# Sheet1.net
KiCad netlist of a schematic drawn in Altium Designer
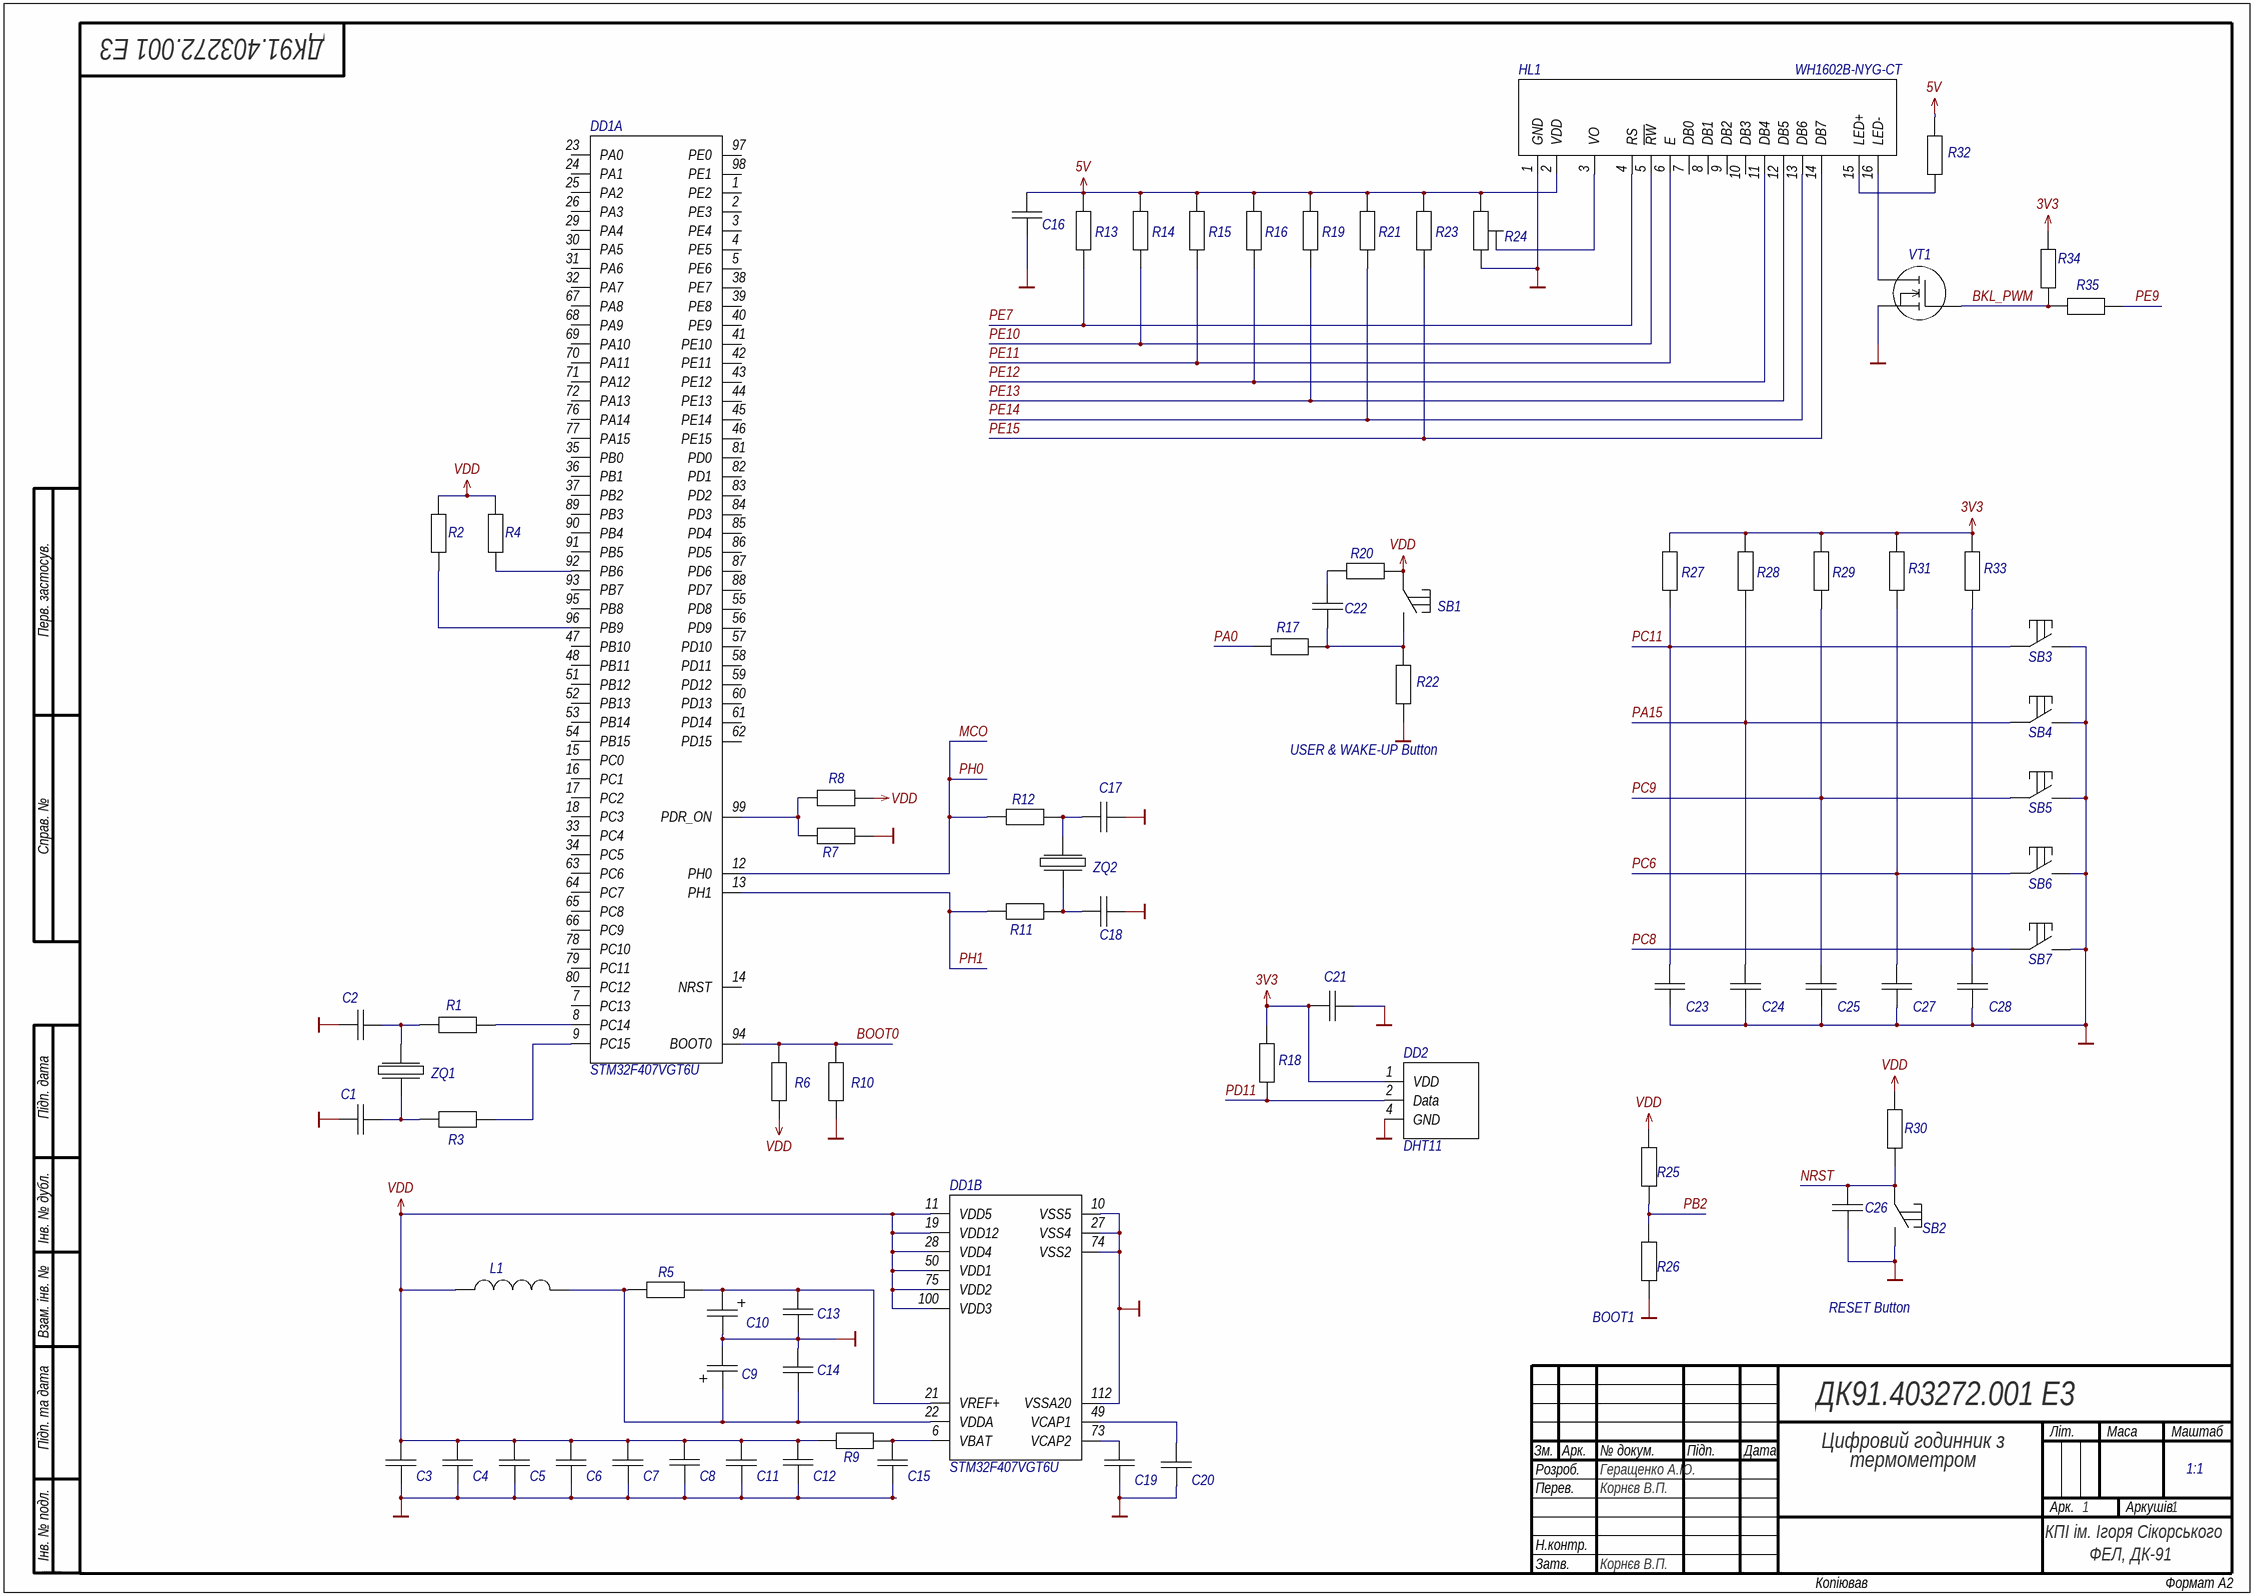
[diagram p0: Sheet1.SchDoc]

(export (version "E")
  (design (tool "Eeschema 10.0.6"))
  (components
    (comp (ref "C1")
      (value "0603 16 В 6,8 пФ 5% C0G, NP0 Kemet")
      (footprint "C-0603, 22 пФ")
      (description "Capasitor 0603")
      (fields (field (name "MANUFACTURER") "Kemet") (field (name "TOLERANCE") "5%"))
      (libsource (lib "Schlib1") (part "C-0603, 6,8 пФ"))
    )
    (comp (ref "C2")
      (value "0603 16 В 6,8 пФ 5% C0G, NP0 Kemet")
      (footprint "C-0603, 22 пФ")
      (description "Capasitor 0603")
      (fields (field (name "MANUFACTURER") "Kemet") (field (name "TOLERANCE") "5%"))
      (libsource (lib "Schlib1") (part "C-0603, 6,8 пФ"))
    )
    (comp (ref "C3")
      (value "0603 16 В 100 нФ 5% X7R Samsung")
      (footprint "C-0603, 100 нФ")
      (description "Capasitor 0603")
      (fields (field (name "MANUFACTURER") "Samsung") (field (name "TOLERANCE") "5%"))
      (libsource (lib "Schlib1") (part "C-0603, 100 нФ"))
    )
    (comp (ref "C4")
      (value "0603 16 В 100 нФ 5% X7R Samsung")
      (footprint "C-0603, 100 нФ")
      (description "Capasitor 0603")
      (fields (field (name "MANUFACTURER") "Samsung") (field (name "TOLERANCE") "5%"))
      (libsource (lib "Schlib1") (part "C-0603, 100 нФ"))
    )
    (comp (ref "C5")
      (value "0603 16 В 100 нФ 5% X7R Samsung")
      (footprint "C-0603, 100 нФ")
      (description "Capasitor 0603")
      (fields (field (name "MANUFACTURER") "Samsung") (field (name "TOLERANCE") "5%"))
      (libsource (lib "Schlib1") (part "C-0603, 100 нФ"))
    )
    (comp (ref "C6")
      (value "0603 16 В 100 нФ 5% X7R Samsung")
      (footprint "C-0603, 100 нФ")
      (description "Capasitor 0603")
      (fields (field (name "MANUFACTURER") "Samsung") (field (name "TOLERANCE") "5%"))
      (libsource (lib "Schlib1") (part "C-0603, 100 нФ"))
    )
    (comp (ref "C7")
      (value "0603 16 В 100 нФ 5% X7R Samsung")
      (footprint "C-0603, 100 нФ")
      (description "Capasitor 0603")
      (fields (field (name "MANUFACTURER") "Samsung") (field (name "TOLERANCE") "5%"))
      (libsource (lib "Schlib1") (part "C-0603, 100 нФ"))
    )
    (comp (ref "C8")
      (value "0603 16 В 100 нФ 5% X7R Samsung")
      (footprint "C-0603, 100 нФ")
      (description "Capasitor 0603")
      (fields (field (name "MANUFACTURER") "Samsung") (field (name "TOLERANCE") "5%"))
      (libsource (lib "Schlib1") (part "C-0603, 100 нФ"))
    )
    (comp (ref "C9")
      (value "1206 16 В 1 мкФ 10% KYOCERA AVX")
      (footprint "C-1206, 10 мкФ")
      (description "Capasitor")
      (fields (field (name "MANUFACTURER") "KYOCERA AVX") (field (name "TOLERANCE") "10%"))
      (libsource (lib "Schlib1") (part "С-1206, 1 мкФ"))
    )
    (comp (ref "C10")
      (value "1206 16 В 1 мкФ 10% KYOCERA AVX")
      (footprint "C-1206, 10 мкФ")
      (description "Capasitor")
      (fields (field (name "MANUFACTURER") "KYOCERA AVX") (field (name "TOLERANCE") "10%"))
      (libsource (lib "Schlib1") (part "С-1206, 1 мкФ"))
    )
    (comp (ref "C11")
      (value "0603 16 В 100 нФ 5% X7R Samsung")
      (footprint "C-0603, 100 нФ")
      (description "Capasitor 0603")
      (fields (field (name "MANUFACTURER") "Samsung") (field (name "TOLERANCE") "5%"))
      (libsource (lib "Schlib1") (part "C-0603, 100 нФ"))
    )
    (comp (ref "C12")
      (value "0603 16 В 100 нФ 5% X7R Samsung")
      (footprint "C-0603, 100 нФ")
      (description "Capasitor 0603")
      (fields (field (name "MANUFACTURER") "Samsung") (field (name "TOLERANCE") "5%"))
      (libsource (lib "Schlib1") (part "C-0603, 100 нФ"))
    )
    (comp (ref "C13")
      (value "0603 16 В 100 нФ 5% X7R Samsung")
      (footprint "C-0603, 100 нФ")
      (description "Capasitor 0603")
      (fields (field (name "MANUFACTURER") "Samsung") (field (name "TOLERANCE") "5%"))
      (libsource (lib "Schlib1") (part "C-0603, 100 нФ"))
    )
    (comp (ref "C14")
      (value "0603 16 В 100 нФ 5% X7R Samsung")
      (footprint "C-0603, 100 нФ")
      (description "Capasitor 0603")
      (fields (field (name "MANUFACTURER") "Samsung") (field (name "TOLERANCE") "5%"))
      (libsource (lib "Schlib1") (part "C-0603, 100 нФ"))
    )
    (comp (ref "C15")
      (value "0603 16 В 1 мкФ 5% X7R Kemet")
      (footprint "C-0603, 1 мкФ")
      (description "Capasitor 0603")
      (fields (field (name "MANUFACTURER") "Kemet") (field (name "TOLERANCE") "5%"))
      (libsource (lib "Schlib1") (part "C-0603, 1 мкФ"))
    )
    (comp (ref "C16")
      (value "0603 16 В 0,1 мкФ 5% X7R Kemet")
      (footprint "C-0603, 1 мкФ")
      (description "Capasitor 0603")
      (fields (field (name "MANUFACTURER") "Kemet") (field (name "TOLERANCE") "5%"))
      (libsource (lib "Schlib1") (part "C-0603, 0,1 мкФ"))
    )
    (comp (ref "C17")
      (value "0603 16 В 20 пФ 5% C0G, NP0 Kemet")
      (footprint "C-0603, 22 пФ")
      (description "Capasitor 0603")
      (fields (field (name "MANUFACTURER") "Kemet") (field (name "TOLERANCE") "5%"))
      (libsource (lib "Schlib1") (part "C-0603, 20 пФ"))
    )
    (comp (ref "C18")
      (value "0603 16 В 20 пФ 5% C0G, NP0 Kemet")
      (footprint "C-0603, 22 пФ")
      (description "Capasitor 0603")
      (fields (field (name "MANUFACTURER") "Kemet") (field (name "TOLERANCE") "5%"))
      (libsource (lib "Schlib1") (part "C-0603, 20 пФ"))
    )
    (comp (ref "C19")
      (value "0603 16 В 2,2 мкФ 5% X7R Kemet")
      (footprint "C-0603, 1 мкФ")
      (description "Capasitor 0603")
      (fields (field (name "MANUFACTURER") "Kemet") (field (name "TOLERANCE") "5%"))
      (libsource (lib "Schlib1") (part "C-0603, 2,2 мкФ"))
    )
    (comp (ref "C20")
      (value "0603 16 В 2,2 мкФ 5% X7R Kemet")
      (footprint "C-0603, 1 мкФ")
      (description "Capasitor 0603")
      (fields (field (name "MANUFACTURER") "Kemet") (field (name "TOLERANCE") "5%"))
      (libsource (lib "Schlib1") (part "C-0603, 2,2 мкФ"))
    )
    (comp (ref "C21")
      (value "0603 16 В 0,1 мкФ 5% X7R Kemet")
      (footprint "C-0603, 1 мкФ")
      (description "Capasitor 0603")
      (fields (field (name "MANUFACTURER") "Kemet") (field (name "TOLERANCE") "5%"))
      (libsource (lib "Schlib1") (part "C-0603, 0,1 мкФ"))
    )
    (comp (ref "C22")
      (value "0603 16 В 100 нФ 5% X7R Samsung")
      (footprint "C-0603, 100 нФ")
      (description "Capasitor 0603")
      (fields (field (name "MANUFACTURER") "Samsung") (field (name "TOLERANCE") "5%"))
      (libsource (lib "Schlib1") (part "C-0603, 100 нФ"))
    )
    (comp (ref "C23")
      (value "0603 16 В 0,01 мкФ 5% X7R Kemet")
      (footprint "C-0603, 1 мкФ")
      (description "Capasitor 0603")
      (fields (field (name "MANUFACTURER") "Kemet") (field (name "TOLERANCE") "5%"))
      (libsource (lib "Schlib1") (part "C-0603, 0,01 мкФ"))
    )
    (comp (ref "C24")
      (value "0603 16 В 0,01 мкФ 5% X7R Kemet")
      (footprint "C-0603, 1 мкФ")
      (description "Capasitor 0603")
      (fields (field (name "MANUFACTURER") "Kemet") (field (name "TOLERANCE") "5%"))
      (libsource (lib "Schlib1") (part "C-0603, 0,01 мкФ"))
    )
    (comp (ref "C25")
      (value "0603 16 В 0,01 мкФ 5% X7R Kemet")
      (footprint "C-0603, 1 мкФ")
      (description "Capasitor 0603")
      (fields (field (name "MANUFACTURER") "Kemet") (field (name "TOLERANCE") "5%"))
      (libsource (lib "Schlib1") (part "C-0603, 0,01 мкФ"))
    )
    (comp (ref "C26")
      (value "0603 16 В 100 нФ 5% X7R Samsung")
      (footprint "C-0603, 100 нФ")
      (description "Capasitor 0603")
      (fields (field (name "MANUFACTURER") "Samsung") (field (name "TOLERANCE") "5%"))
      (libsource (lib "Schlib1") (part "C-0603, 100 нФ"))
    )
    (comp (ref "C27")
      (value "0603 16 В 0,01 мкФ 5% X7R Kemet")
      (footprint "C-0603, 1 мкФ")
      (description "Capasitor 0603")
      (fields (field (name "MANUFACTURER") "Kemet") (field (name "TOLERANCE") "5%"))
      (libsource (lib "Schlib1") (part "C-0603, 0,01 мкФ"))
    )
    (comp (ref "C28")
      (value "0603 16 В 0,01 мкФ 5% X7R Kemet")
      (footprint "C-0603, 1 мкФ")
      (description "Capasitor 0603")
      (fields (field (name "MANUFACTURER") "Kemet") (field (name "TOLERANCE") "5%"))
      (libsource (lib "Schlib1") (part "C-0603, 0,01 мкФ"))
    )
    (comp (ref "DD1")
      (value "STM32F407VGT6U STMicroelectronics")
      (fields (field (name "NAME") "STM32F407VGT6U") (field (name "MANUFACTURER") "STMicroelectronics"))
      (libsource (lib "Schlib1") (part "STM32F407VGT6U"))
    )
    (comp (ref "DD2")
      (value "DHT11 Asair")
      (fields (field (name "NAME") "DHT11") (field (name "MANUFACTURER") "Asair"))
      (libsource (lib "Schlib1") (part "dht11"))
    )
    (comp (ref "HL1")
      (value "WH1602B-NYG-CT WINSTAR")
      (fields (field (name "NAME") "WH1602B-NYG-CT") (field (name "MANUFACTURER") "WINSTAR"))
      (libsource (lib "Schlib1") (part "lcd"))
    )
    (comp (ref "L1")
      (value "fcm1608-0603 Bourns Electronics")
      (footprint "IND_BOURNS_MH2029")
      (description "fcm1608-0603")
      (fields (field (name "MANUFACTURER") "Bourns Electronics"))
      (libsource (lib "Schlib1") (part "fcm1608-0603"))
    )
    (comp (ref "R1")
      (value "0603 0,1 Вт 0 Ом Jumper Panasonic")
      (footprint "R-0603, 0 Ом")
      (description "Resistor 0603")
      (fields (field (name "MANUFACTURER") "Panasonic") (field (name "TOLERANCE") "Jumper"))
      (libsource (lib "Schlib1") (part "R-0603, 0 Ом"))
    )
    (comp (ref "R2")
      (value "0603 0,25 Вт 4,7 кОм 5% Panasonic")
      (footprint "R-0603, 6,8 кОм")
      (description "Resistor 0603")
      (fields (field (name "MANUFACTURER") "Panasonic") (field (name "TOLERANCE") "5%"))
      (libsource (lib "Schlib1") (part "R-0603, 4,7 кОм"))
    )
    (comp (ref "R3")
      (value "0603 0,1 Вт 0 Ом Jumper Panasonic")
      (footprint "R-0603, 0 Ом")
      (description "Resistor 0603")
      (fields (field (name "MANUFACTURER") "Panasonic") (field (name "TOLERANCE") "Jumper"))
      (libsource (lib "Schlib1") (part "R-0603, 0 Ом"))
    )
    (comp (ref "R4")
      (value "0603 0,25 Вт 4,7 кОм 5% Panasonic")
      (footprint "R-0603, 6,8 кОм")
      (description "Resistor 0603")
      (fields (field (name "MANUFACTURER") "Panasonic") (field (name "TOLERANCE") "5%"))
      (libsource (lib "Schlib1") (part "R-0603, 4,7 кОм"))
    )
    (comp (ref "R5")
      (value "R-0603 0,1 Вт 47 Ом 5% Panasonic Electronic Components")
      (footprint "0603 47 Ом")
      (fields
        (field (name "POWER") "0,1 Вт")
        (field (name "TOLERANCE") "5%")
        (field (name "MANUFACTURER") "Panasonic Electronic Components")
      )
      (libsource (lib "Schlib1") (part "R-0603 47 Ом"))
    )
    (comp (ref "R6")
      (value "0603 0,25 Вт 10 кОм 5% Panasonic")
      (footprint "R-0603, 10 кОм")
      (description "Resistor 0603")
      (fields (field (name "MANUFACTURER") "Panasonic") (field (name "TOLERANCE") "5%"))
      (libsource (lib "Schlib1") (part "R-0603, 10 кОм"))
    )
    (comp (ref "R7")
      (value "0603 0,1 Вт 0 Ом Jumper Panasonic")
      (footprint "R-0603, 0 Ом")
      (description "Resistor 0603")
      (fields (field (name "MANUFACTURER") "Panasonic") (field (name "TOLERANCE") "Jumper"))
      (libsource (lib "Schlib1") (part "R-0603, 0 Ом"))
    )
    (comp (ref "R8")
      (value "0603 0,1 Вт 0 Ом Jumper Panasonic")
      (footprint "R-0603, 0 Ом")
      (description "Resistor 0603")
      (fields (field (name "MANUFACTURER") "Panasonic") (field (name "TOLERANCE") "Jumper"))
      (libsource (lib "Schlib1") (part "R-0603, 0 Ом"))
    )
    (comp (ref "R9")
      (value "0603 0,1 Вт 0 Ом Jumper Panasonic")
      (footprint "R-0603, 0 Ом")
      (description "Resistor 0603")
      (fields (field (name "MANUFACTURER") "Panasonic") (field (name "TOLERANCE") "Jumper"))
      (libsource (lib "Schlib1") (part "R-0603, 0 Ом"))
    )
    (comp (ref "R10")
      (value "R-0603 0,1 Вт 510 Ом 5% Panasonic Electronic Components")
      (footprint "0603 330 Ом")
      (fields
        (field (name "POWER") "0,1 Вт")
        (field (name "TOLERANCE") "5%")
        (field (name "MANUFACTURER") "Panasonic Electronic Components")
      )
      (libsource (lib "Schlib1") (part "R-0603 510 Ом"))
    )
    (comp (ref "R11")
      (value "R-0603 0,1 Вт 220 Ом 5% Panasonic Electronic Components")
      (footprint "0603 270 Ом")
      (fields
        (field (name "POWER") "0,1 Вт")
        (field (name "TOLERANCE") "5%")
        (field (name "MANUFACTURER") "Panasonic Electronic Components")
      )
      (libsource (lib "Schlib1") (part "R-0603 220 Ом"))
    )
    (comp (ref "R12")
      (value "0603 0,1 Вт 0 Ом Jumper Panasonic")
      (footprint "R-0603, 0 Ом")
      (description "Resistor 0603")
      (fields (field (name "MANUFACTURER") "Panasonic") (field (name "TOLERANCE") "Jumper"))
      (libsource (lib "Schlib1") (part "R-0603, 0 Ом"))
    )
    (comp (ref "R13")
      (value "0603 0,25 Вт 4,7 кОм 5% Panasonic")
      (footprint "R-0603, 6,8 кОм")
      (description "Resistor 0603")
      (fields (field (name "MANUFACTURER") "Panasonic") (field (name "TOLERANCE") "5%"))
      (libsource (lib "Schlib1") (part "R-0603, 4,7 кОм"))
    )
    (comp (ref "R14")
      (value "0603 0,25 Вт 4,7 кОм 5% Panasonic")
      (footprint "R-0603, 6,8 кОм")
      (description "Resistor 0603")
      (fields (field (name "MANUFACTURER") "Panasonic") (field (name "TOLERANCE") "5%"))
      (libsource (lib "Schlib1") (part "R-0603, 4,7 кОм"))
    )
    (comp (ref "R15")
      (value "0603 0,25 Вт 4,7 кОм 5% Panasonic")
      (footprint "R-0603, 6,8 кОм")
      (description "Resistor 0603")
      (fields (field (name "MANUFACTURER") "Panasonic") (field (name "TOLERANCE") "5%"))
      (libsource (lib "Schlib1") (part "R-0603, 4,7 кОм"))
    )
    (comp (ref "R16")
      (value "0603 0,25 Вт 4,7 кОм 5% Panasonic")
      (footprint "R-0603, 6,8 кОм")
      (description "Resistor 0603")
      (fields (field (name "MANUFACTURER") "Panasonic") (field (name "TOLERANCE") "5%"))
      (libsource (lib "Schlib1") (part "R-0603, 4,7 кОм"))
    )
    (comp (ref "R17")
      (value "R-0603 0,1 Вт 330 Ом 5% Panasonic Electronic Components")
      (footprint "0603 330 Ом")
      (fields
        (field (name "POWER") "0,1 Вт")
        (field (name "TOLERANCE") "5%")
        (field (name "MANUFACTURER") "Panasonic Electronic Components")
      )
      (libsource (lib "Schlib1") (part "R-0603 330 Ом"))
    )
    (comp (ref "R18")
      (value "0603 0,25 Вт 2 кОм 5% Panasonic")
      (footprint "R-0603, 1кОм")
      (description "Resistor 0603")
      (fields (field (name "MANUFACTURER") "Panasonic") (field (name "TOLERANCE") "5%"))
      (libsource (lib "Schlib1") (part "R-0603, 2кОм"))
    )
    (comp (ref "R19")
      (value "0603 0,25 Вт 4,7 кОм 5% Panasonic")
      (footprint "R-0603, 6,8 кОм")
      (description "Resistor 0603")
      (fields (field (name "MANUFACTURER") "Panasonic") (field (name "TOLERANCE") "5%"))
      (libsource (lib "Schlib1") (part "R-0603, 4,7 кОм"))
    )
    (comp (ref "R20")
      (value "R-0603  100 Ом 5% Panasonic Electronic Components")
      (footprint "0603 100 Ом")
      (fields (field (name "TOLERANCE") "5%") (field (name "MANUFACTURER") "Panasonic Electronic Components"))
      (libsource (lib "Schlib1") (part "R-0603 100 Ом"))
    )
    (comp (ref "R21")
      (value "0603 0,25 Вт 4,7 кОм 5% Panasonic")
      (footprint "R-0603, 6,8 кОм")
      (description "Resistor 0603")
      (fields (field (name "MANUFACTURER") "Panasonic") (field (name "TOLERANCE") "5%"))
      (libsource (lib "Schlib1") (part "R-0603, 4,7 кОм"))
    )
    (comp (ref "R22")
      (value "R-0603 0,1 Вт 220 кОм 5% Panasonic Electronic Components")
      (footprint "0603 330 кОм")
      (fields
        (field (name "POWER") "0,1 Вт")
        (field (name "TOLERANCE") "5%")
        (field (name "MANUFACTURER") "Panasonic Electronic Components")
      )
      (libsource (lib "Schlib1") (part "R-0603 220 кОм"))
    )
    (comp (ref "R23")
      (value "0603 0,25 Вт 4,7 кОм 5% Panasonic")
      (footprint "R-0603, 6,8 кОм")
      (description "Resistor 0603")
      (fields (field (name "MANUFACTURER") "Panasonic") (field (name "TOLERANCE") "5%"))
      (libsource (lib "Schlib1") (part "R-0603, 4,7 кОм"))
    )
    (comp (ref "R24")
      (value "Tube 0,5 Вт 10 кОм 10% Bourns Inc.")
      (footprint "R-Tube")
      (fields
        (field (name "POWER") "0,5 Вт")
        (field (name "TOLERANCE") "10%")
        (field (name "MANUFACTURER") "Bourns Inc.")
      )
      (libsource (lib "Schlib1") (part "R-Tube 10 кОм"))
    )
    (comp (ref "R25")
      (value "0603 0,25 Вт 10 кОм 5% Panasonic")
      (footprint "R-0603, 10 кОм")
      (description "Resistor 0603")
      (fields (field (name "MANUFACTURER") "Panasonic") (field (name "TOLERANCE") "5%"))
      (libsource (lib "Schlib1") (part "R-0603, 10 кОм"))
    )
    (comp (ref "R26")
      (value "R-0603 0,1 Вт 510 Ом 5% Panasonic Electronic Components")
      (footprint "0603 330 Ом")
      (fields
        (field (name "POWER") "0,1 Вт")
        (field (name "TOLERANCE") "5%")
        (field (name "MANUFACTURER") "Panasonic Electronic Components")
      )
      (libsource (lib "Schlib1") (part "R-0603 510 Ом"))
    )
    (comp (ref "R27")
      (value "0603 0,25 Вт 4,7 кОм 5% Panasonic")
      (footprint "R-0603, 6,8 кОм")
      (description "Resistor 0603")
      (fields (field (name "MANUFACTURER") "Panasonic") (field (name "TOLERANCE") "5%"))
      (libsource (lib "Schlib1") (part "R-0603, 4,7 кОм"))
    )
    (comp (ref "R28")
      (value "0603 0,25 Вт 4,7 кОм 5% Panasonic")
      (footprint "R-0603, 6,8 кОм")
      (description "Resistor 0603")
      (fields (field (name "MANUFACTURER") "Panasonic") (field (name "TOLERANCE") "5%"))
      (libsource (lib "Schlib1") (part "R-0603, 4,7 кОм"))
    )
    (comp (ref "R29")
      (value "0603 0,25 Вт 4,7 кОм 5% Panasonic")
      (footprint "R-0603, 6,8 кОм")
      (description "Resistor 0603")
      (fields (field (name "MANUFACTURER") "Panasonic") (field (name "TOLERANCE") "5%"))
      (libsource (lib "Schlib1") (part "R-0603, 4,7 кОм"))
    )
    (comp (ref "R30")
      (value "0603 0,25 Вт 100 кОм 5% Panasonic")
      (footprint "R-0603, 100 кОм")
      (description "Resistor 0603")
      (fields (field (name "MANUFACTURER") "Panasonic") (field (name "TOLERANCE") "5%"))
      (libsource (lib "Schlib1") (part "R-0603, 100 кОм"))
    )
    (comp (ref "R31")
      (value "0603 0,25 Вт 4,7 кОм 5% Panasonic")
      (footprint "R-0603, 6,8 кОм")
      (description "Resistor 0603")
      (fields (field (name "MANUFACTURER") "Panasonic") (field (name "TOLERANCE") "5%"))
      (libsource (lib "Schlib1") (part "R-0603, 4,7 кОм"))
    )
    (comp (ref "R32")
      (value "R-0603  100 Ом 5% Panasonic Electronic Components")
      (footprint "0603 100 Ом")
      (fields (field (name "TOLERANCE") "5%") (field (name "MANUFACTURER") "Panasonic Electronic Components"))
      (libsource (lib "") (part "R-0603 100 Ом_1"))
    )
    (comp (ref "R33")
      (value "0603 0,25 Вт 4,7 кОм 5% Panasonic")
      (footprint "R-0603, 6,8 кОм")
      (description "Resistor 0603")
      (fields (field (name "MANUFACTURER") "Panasonic") (field (name "TOLERANCE") "5%"))
      (libsource (lib "Schlib1") (part "R-0603, 4,7 кОм"))
    )
    (comp (ref "R34")
      (value "0603 0,25 Вт 4,7 кОм 5% Panasonic")
      (footprint "R-0603, 6,8 кОм")
      (description "Resistor 0603")
      (fields (field (name "MANUFACTURER") "Panasonic") (field (name "TOLERANCE") "5%"))
      (libsource (lib "Schlib1") (part "R-0603, 4,7 кОм"))
    )
    (comp (ref "R35")
      (value "R-0603  100 Ом 5% Panasonic Electronic Components")
      (footprint "0603 100 Ом")
      (fields (field (name "TOLERANCE") "5%") (field (name "MANUFACTURER") "Panasonic Electronic Components"))
      (libsource (lib "Schlib1") (part "R-0603 100 Ом"))
    )
    (comp (ref "SB1")
      (value "RS032G05A3SMRT C&K")
      (footprint "SB 2 pin")
      (description "Tactile Switch SPST-NO Top Actuated Surface Mount")
      (fields (field (name "MANUFACTURER") "C&K"))
      (libsource (lib "Schlib1") (part "SB 2pin"))
    )
    (comp (ref "SB2")
      (value "RS032G05A3SMRT C&K")
      (footprint "SB 2 pin")
      (description "Tactile Switch SPST-NO Top Actuated Surface Mount")
      (fields (field (name "MANUFACTURER") "C&K"))
      (libsource (lib "Schlib1") (part "SB 2pin"))
    )
    (comp (ref "SB3")
      (value "RS032G05A3SMRT C&K")
      (footprint "SB 2 pin")
      (description "Tactile Switch SPST-NO Top Actuated Surface Mount")
      (fields (field (name "MANUFACTURER") "C&K"))
      (libsource (lib "Schlib1") (part "SB 2pin"))
    )
    (comp (ref "SB4")
      (value "RS032G05A3SMRT C&K")
      (footprint "SB 2 pin")
      (description "Tactile Switch SPST-NO Top Actuated Surface Mount")
      (fields (field (name "MANUFACTURER") "C&K"))
      (libsource (lib "Schlib1") (part "SB 2pin"))
    )
    (comp (ref "SB5")
      (value "RS032G05A3SMRT C&K")
      (footprint "SB 2 pin")
      (description "Tactile Switch SPST-NO Top Actuated Surface Mount")
      (fields (field (name "MANUFACTURER") "C&K"))
      (libsource (lib "Schlib1") (part "SB 2pin"))
    )
    (comp (ref "SB6")
      (value "RS032G05A3SMRT C&K")
      (footprint "SB 2 pin")
      (description "Tactile Switch SPST-NO Top Actuated Surface Mount")
      (fields (field (name "MANUFACTURER") "C&K"))
      (libsource (lib "Schlib1") (part "SB 2pin"))
    )
    (comp (ref "SB7")
      (value "RS032G05A3SMRT C&K")
      (footprint "SB 2 pin")
      (description "Tactile Switch SPST-NO Top Actuated Surface Mount")
      (fields (field (name "MANUFACTURER") "C&K"))
      (libsource (lib "Schlib1") (part "SB 2pin"))
    )
    (comp (ref "VT1")
      (value "IRLML2402TRPBF Infineon Technologies")
      (footprint "VT IRFZ44NLPBF")
      (fields (field (name "MANUFACTURER") "Infineon Technologies"))
      (libsource (lib "Schlib1") (part "VT IRLML2402TRPBF"))
    )
    (comp (ref "ZQ1")
      (value "MC306-G-06Q-32.768 JFVNY")
      (footprint "ZQ 32,768 kHz")
      (fields (field (name "MANUFACTURER") "JFVNY"))
      (libsource (lib "Schlib1") (part "ZQ 32,768 kHz"))
    )
    (comp (ref "ZQ2")
      (value "J49SMH-P-G-G-K-8M0 Jauch Quartz")
      (footprint "ZQ 32,768 kHz")
      (fields (field (name "MANUFACTURER") "Jauch Quartz"))
      (libsource (lib "Schlib1") (part "ZQ 8 MHz"))
    )
  )
  (nets
    (net (code "1") (name "/BKL_PWM") (class "Default")
      (node (ref "R34") (pin "1") (pinfunction "1_1") (pintype "passive"))
      (node (ref "R35") (pin "1") (pinfunction "1_1") (pintype "passive"))
      (node (ref "VT1") (pin "1") (pinfunction "1_1") (pintype "passive"))
    )
    (net (code "2") (name "/BOOT0") (class "Default")
      (node (ref "DD1") (pin "94") (pinfunction "BOOT0_94") (pintype "passive"))
      (node (ref "R10") (pin "2") (pinfunction "2_2") (pintype "passive"))
      (node (ref "R6") (pin "2") (pinfunction "2_2") (pintype "passive"))
    )
    (net (code "3") (name "/MCO") (class "Default")
      (node (ref "DD1") (pin "12") (pinfunction "PH0_12") (pintype "passive"))
      (node (ref "R12") (pin "1") (pinfunction "1_1") (pintype "passive"))
    )
    (net (code "4") (name "/NRST") (class "Default")
      (node (ref "C26") (pin "2") (pinfunction "2_2") (pintype "passive"))
      (node (ref "R30") (pin "1") (pinfunction "1_1") (pintype "passive"))
      (node (ref "SB2") (pin "1") (pinfunction "1_1") (pintype "passive"))
    )
    (net (code "5") (name "/PA0") (class "Default")
      (node (ref "R17") (pin "1") (pinfunction "1_1") (pintype "passive"))
    )
    (net (code "6") (name "/PA15") (class "Default")
      (node (ref "C24") (pin "2") (pinfunction "2_2") (pintype "passive"))
      (node (ref "R28") (pin "1") (pinfunction "1_1") (pintype "passive"))
      (node (ref "SB4") (pin "1") (pinfunction "1_1") (pintype "passive"))
    )
    (net (code "7") (name "/PB2") (class "Default")
      (node (ref "R25") (pin "1") (pinfunction "1_1") (pintype "passive"))
      (node (ref "R26") (pin "2") (pinfunction "2_2") (pintype "passive"))
    )
    (net (code "8") (name "/PC6") (class "Default")
      (node (ref "C27") (pin "2") (pinfunction "2_2") (pintype "passive"))
      (node (ref "R31") (pin "1") (pinfunction "1_1") (pintype "passive"))
      (node (ref "SB6") (pin "1") (pinfunction "1_1") (pintype "passive"))
    )
    (net (code "9") (name "/PC8") (class "Default")
      (node (ref "C28") (pin "2") (pinfunction "2_2") (pintype "passive"))
      (node (ref "R33") (pin "1") (pinfunction "1_1") (pintype "passive"))
      (node (ref "SB7") (pin "1") (pinfunction "1_1") (pintype "passive"))
    )
    (net (code "10") (name "/PC9") (class "Default")
      (node (ref "C25") (pin "2") (pinfunction "2_2") (pintype "passive"))
      (node (ref "R29") (pin "1") (pinfunction "1_1") (pintype "passive"))
      (node (ref "SB5") (pin "1") (pinfunction "1_1") (pintype "passive"))
    )
    (net (code "11") (name "/PC11") (class "Default")
      (node (ref "C23") (pin "2") (pinfunction "2_2") (pintype "passive"))
      (node (ref "R27") (pin "1") (pinfunction "1_1") (pintype "passive"))
      (node (ref "SB3") (pin "1") (pinfunction "1_1") (pintype "passive"))
    )
    (net (code "12") (name "/PD11") (class "Default")
      (node (ref "DD2") (pin "2") (pinfunction "Data_2") (pintype "passive"))
      (node (ref "R18") (pin "1") (pinfunction "1_1") (pintype "passive"))
    )
    (net (code "13") (name "/PE7") (class "Default")
      (node (ref "HL1") (pin "4") (pinfunction "RS_4") (pintype "passive"))
      (node (ref "R13") (pin "1") (pinfunction "1_1") (pintype "passive"))
    )
    (net (code "14") (name "/PE9") (class "Default")
      (node (ref "R35") (pin "2") (pinfunction "2_2") (pintype "passive"))
    )
    (net (code "15") (name "/PE10") (class "Default")
      (node (ref "HL1") (pin "5") (pinfunction "~{RW}_5") (pintype "passive"))
      (node (ref "R14") (pin "1") (pinfunction "1_1") (pintype "passive"))
    )
    (net (code "16") (name "/PE11") (class "Default")
      (node (ref "HL1") (pin "6") (pinfunction "E_6") (pintype "passive"))
      (node (ref "R15") (pin "1") (pinfunction "1_1") (pintype "passive"))
    )
    (net (code "17") (name "/PE12") (class "Default")
      (node (ref "HL1") (pin "11") (pinfunction "DB4_11") (pintype "passive"))
      (node (ref "R16") (pin "1") (pinfunction "1_1") (pintype "passive"))
    )
    (net (code "18") (name "/PE13") (class "Default")
      (node (ref "HL1") (pin "12") (pinfunction "DB5_12") (pintype "passive"))
      (node (ref "R19") (pin "1") (pinfunction "1_1") (pintype "passive"))
    )
    (net (code "19") (name "/PE14") (class "Default")
      (node (ref "HL1") (pin "13") (pinfunction "DB6_13") (pintype "passive"))
      (node (ref "R21") (pin "1") (pinfunction "1_1") (pintype "passive"))
    )
    (net (code "20") (name "/PE15") (class "Default")
      (node (ref "HL1") (pin "14") (pinfunction "DB7_14") (pintype "passive"))
      (node (ref "R23") (pin "1") (pinfunction "1_1") (pintype "passive"))
    )
    (net (code "21") (name "/PH1") (class "Default")
      (node (ref "DD1") (pin "13") (pinfunction "PH1_13") (pintype "passive"))
      (node (ref "R11") (pin "1") (pinfunction "1_1") (pintype "passive"))
    )
    (net (code "22") (name "3V3") (class "Default")
      (node (ref "C21") (pin "1") (pinfunction "1_1") (pintype "passive"))
      (node (ref "DD2") (pin "1") (pinfunction "VDD_1") (pintype "passive"))
      (node (ref "R18") (pin "2") (pinfunction "2_2") (pintype "passive"))
      (node (ref "R27") (pin "2") (pinfunction "2_2") (pintype "passive"))
      (node (ref "R28") (pin "2") (pinfunction "2_2") (pintype "passive"))
      (node (ref "R29") (pin "2") (pinfunction "2_2") (pintype "passive"))
      (node (ref "R31") (pin "2") (pinfunction "2_2") (pintype "passive"))
      (node (ref "R33") (pin "2") (pinfunction "2_2") (pintype "passive"))
      (node (ref "R34") (pin "2") (pinfunction "2_2") (pintype "passive"))
    )
    (net (code "23") (name "5V") (class "Default")
      (node (ref "C16") (pin "2") (pinfunction "2_2") (pintype "passive"))
      (node (ref "HL1") (pin "2") (pinfunction "VDD_2") (pintype "passive"))
      (node (ref "R13") (pin "2") (pinfunction "2_2") (pintype "passive"))
      (node (ref "R14") (pin "2") (pinfunction "2_2") (pintype "passive"))
      (node (ref "R15") (pin "2") (pinfunction "2_2") (pintype "passive"))
      (node (ref "R16") (pin "2") (pinfunction "2_2") (pintype "passive"))
      (node (ref "R19") (pin "2") (pinfunction "2_2") (pintype "passive"))
      (node (ref "R21") (pin "2") (pinfunction "2_2") (pintype "passive"))
      (node (ref "R23") (pin "2") (pinfunction "2_2") (pintype "passive"))
      (node (ref "R24") (pin "1") (pinfunction "1_1") (pintype "passive"))
      (node (ref "R32") (pin "2") (pinfunction "2_2") (pintype "passive"))
    )
    (net (code "24") (name "GND") (class "Default")
      (node (ref "C1") (pin "1") (pinfunction "1_1") (pintype "passive"))
      (node (ref "C10") (pin "2") (pinfunction "2_2") (pintype "passive"))
      (node (ref "C11") (pin "1") (pinfunction "1_1") (pintype "passive"))
      (node (ref "C12") (pin "2") (pinfunction "2_2") (pintype "passive"))
      (node (ref "C13") (pin "1") (pinfunction "1_1") (pintype "passive"))
      (node (ref "C14") (pin "1") (pinfunction "1_1") (pintype "passive"))
      (node (ref "C15") (pin "1") (pinfunction "1_1") (pintype "passive"))
      (node (ref "C16") (pin "1") (pinfunction "1_1") (pintype "passive"))
      (node (ref "C17") (pin "2") (pinfunction "2_2") (pintype "passive"))
      (node (ref "C18") (pin "2") (pinfunction "2_2") (pintype "passive"))
      (node (ref "C19") (pin "1") (pinfunction "1_1") (pintype "passive"))
      (node (ref "C2") (pin "1") (pinfunction "1_1") (pintype "passive"))
      (node (ref "C20") (pin "1") (pinfunction "1_1") (pintype "passive"))
      (node (ref "C21") (pin "2") (pinfunction "2_2") (pintype "passive"))
      (node (ref "C23") (pin "1") (pinfunction "1_1") (pintype "passive"))
      (node (ref "C24") (pin "1") (pinfunction "1_1") (pintype "passive"))
      (node (ref "C25") (pin "1") (pinfunction "1_1") (pintype "passive"))
      (node (ref "C26") (pin "1") (pinfunction "1_1") (pintype "passive"))
      (node (ref "C27") (pin "1") (pinfunction "1_1") (pintype "passive"))
      (node (ref "C28") (pin "1") (pinfunction "1_1") (pintype "passive"))
      (node (ref "C3") (pin "1") (pinfunction "1_1") (pintype "passive"))
      (node (ref "C4") (pin "1") (pinfunction "1_1") (pintype "passive"))
      (node (ref "C5") (pin "1") (pinfunction "1_1") (pintype "passive"))
      (node (ref "C6") (pin "1") (pinfunction "1_1") (pintype "passive"))
      (node (ref "C7") (pin "1") (pinfunction "1_1") (pintype "passive"))
      (node (ref "C8") (pin "2") (pinfunction "2_2") (pintype "passive"))
      (node (ref "C9") (pin "2") (pinfunction "2_2") (pintype "passive"))
      (node (ref "DD1") (pin "10") (pinfunction "VSS5_10") (pintype "passive"))
      (node (ref "DD1") (pin "112") (pinfunction "VSSA20_112") (pintype "passive"))
      (node (ref "DD1") (pin "27") (pinfunction "VSS4_27") (pintype "passive"))
      (node (ref "DD1") (pin "74") (pinfunction "VSS2_74") (pintype "passive"))
      (node (ref "DD2") (pin "4") (pinfunction "GND_4") (pintype "passive"))
      (node (ref "HL1") (pin "1") (pinfunction "GND_1") (pintype "passive"))
      (node (ref "R10") (pin "1") (pinfunction "1_1") (pintype "passive"))
      (node (ref "R22") (pin "1") (pinfunction "1_1") (pintype "passive"))
      (node (ref "R24") (pin "3") (pinfunction "3_3") (pintype "passive"))
      (node (ref "R26") (pin "1") (pinfunction "1_1") (pintype "passive"))
      (node (ref "R7") (pin "2") (pinfunction "2_2") (pintype "passive"))
      (node (ref "SB2") (pin "2") (pinfunction "2_2") (pintype "passive"))
      (node (ref "SB3") (pin "2") (pinfunction "2_2") (pintype "passive"))
      (node (ref "SB4") (pin "2") (pinfunction "2_2") (pintype "passive"))
      (node (ref "SB5") (pin "2") (pinfunction "2_2") (pintype "passive"))
      (node (ref "SB6") (pin "2") (pinfunction "2_2") (pintype "passive"))
      (node (ref "SB7") (pin "2") (pinfunction "2_2") (pintype "passive"))
      (node (ref "VT1") (pin "3") (pinfunction "3_3") (pintype "passive"))
    )
    (net (code "25") (name "Net-(C22-Pad1)") (class "Default")
      (node (ref "C22") (pin "1") (pinfunction "1_1") (pintype "passive"))
      (node (ref "R17") (pin "2") (pinfunction "2_2") (pintype "passive"))
      (node (ref "R22") (pin "2") (pinfunction "2_2") (pintype "passive"))
      (node (ref "SB1") (pin "2") (pinfunction "2_2") (pintype "passive"))
    )
    (net (code "26") (name "Net-(C22-Pad2)") (class "Default")
      (node (ref "C22") (pin "2") (pinfunction "2_2") (pintype "passive"))
      (node (ref "R20") (pin "1") (pinfunction "1_1") (pintype "passive"))
    )
    (net (code "27") (name "Net-(DD1A-PB6)") (class "Default")
      (node (ref "DD1") (pin "92") (pinfunction "PB6_92") (pintype "passive"))
      (node (ref "R4") (pin "1") (pinfunction "1_1") (pintype "passive"))
    )
    (net (code "28") (name "Net-(DD1A-PB9)") (class "Default")
      (node (ref "DD1") (pin "96") (pinfunction "PB9_96") (pintype "passive"))
      (node (ref "R2") (pin "1") (pinfunction "1_1") (pintype "passive"))
    )
    (net (code "29") (name "Net-(DD1A-PC14)") (class "Default")
      (node (ref "DD1") (pin "8") (pinfunction "PC14_8") (pintype "passive"))
      (node (ref "R1") (pin "2") (pinfunction "2_2") (pintype "passive"))
    )
    (net (code "30") (name "Net-(DD1A-PC15)") (class "Default")
      (node (ref "DD1") (pin "9") (pinfunction "PC15_9") (pintype "passive"))
      (node (ref "R3") (pin "2") (pinfunction "2_2") (pintype "passive"))
    )
    (net (code "31") (name "Net-(DD1A-PDR_ON)") (class "Default")
      (node (ref "DD1") (pin "99") (pinfunction "PDR_ON_99") (pintype "passive"))
      (node (ref "R7") (pin "1") (pinfunction "1_1") (pintype "passive"))
      (node (ref "R8") (pin "1") (pinfunction "1_1") (pintype "passive"))
    )
    (net (code "32") (name "Net-(DD1B-VBAT)") (class "Default")
      (node (ref "C15") (pin "2") (pinfunction "2_2") (pintype "passive"))
      (node (ref "DD1") (pin "6") (pinfunction "VBAT_6") (pintype "passive"))
      (node (ref "R9") (pin "2") (pinfunction "2_2") (pintype "passive"))
    )
    (net (code "33") (name "Net-(DD1B-VCAP1)") (class "Default")
      (node (ref "C20") (pin "2") (pinfunction "2_2") (pintype "passive"))
      (node (ref "DD1") (pin "49") (pinfunction "VCAP1_49") (pintype "passive"))
    )
    (net (code "34") (name "Net-(DD1B-VCAP2)") (class "Default")
      (node (ref "C19") (pin "2") (pinfunction "2_2") (pintype "passive"))
      (node (ref "DD1") (pin "73") (pinfunction "VCAP2_73") (pintype "passive"))
    )
    (net (code "35") (name "Net-(DD1B-VDDA)") (class "Default")
      (node (ref "C14") (pin "2") (pinfunction "2_2") (pintype "passive"))
      (node (ref "C9") (pin "1") (pinfunction "1_1") (pintype "passive"))
      (node (ref "DD1") (pin "22") (pinfunction "VDDA_22") (pintype "passive"))
      (node (ref "L1") (pin "2") (pinfunction "2_2") (pintype "passive"))
      (node (ref "R5") (pin "1") (pinfunction "1_1") (pintype "passive"))
    )
    (net (code "36") (name "Net-(DD1B-VREF+)") (class "Default")
      (node (ref "C10") (pin "1") (pinfunction "1_1") (pintype "passive"))
      (node (ref "C13") (pin "2") (pinfunction "2_2") (pintype "passive"))
      (node (ref "DD1") (pin "21") (pinfunction "VREF+_21") (pintype "passive"))
      (node (ref "R5") (pin "2") (pinfunction "2_2") (pintype "passive"))
    )
    (net (code "37") (name "Net-(HL1-LED+)") (class "Default")
      (node (ref "HL1") (pin "15") (pinfunction "LED+_15") (pintype "passive"))
      (node (ref "R32") (pin "1") (pinfunction "1_1") (pintype "passive"))
    )
    (net (code "38") (name "Net-(HL1-LED-)") (class "Default")
      (node (ref "HL1") (pin "16") (pinfunction "LED-_16") (pintype "passive"))
      (node (ref "VT1") (pin "2") (pinfunction "2_2") (pintype "passive"))
    )
    (net (code "39") (name "Net-(HL1-VO)") (class "Default")
      (node (ref "HL1") (pin "3") (pinfunction "VO_3") (pintype "passive"))
      (node (ref "R24") (pin "2") (pinfunction "2_2") (pintype "passive"))
    )
    (net (code "40") (name "Net-(ZQ1-In{slash}Out)") (class "Default")
      (node (ref "C1") (pin "2") (pinfunction "2_2") (pintype "passive"))
      (node (ref "R3") (pin "1") (pinfunction "1_1") (pintype "passive"))
      (node (ref "ZQ1") (pin "1") (pinfunction "In/Out_1") (pintype "passive"))
    )
    (net (code "41") (name "Net-(ZQ1-Out{slash}In)") (class "Default")
      (node (ref "C2") (pin "2") (pinfunction "2_2") (pintype "passive"))
      (node (ref "R1") (pin "1") (pinfunction "1_1") (pintype "passive"))
      (node (ref "ZQ1") (pin "2") (pinfunction "Out/In_2") (pintype "passive"))
    )
    (net (code "42") (name "Net-(ZQ2-In{slash}Out)") (class "Default")
      (node (ref "C18") (pin "1") (pinfunction "1_1") (pintype "passive"))
      (node (ref "R11") (pin "2") (pinfunction "2_2") (pintype "passive"))
      (node (ref "ZQ2") (pin "1") (pinfunction "In/Out_1") (pintype "passive"))
    )
    (net (code "43") (name "Net-(ZQ2-Out{slash}In)") (class "Default")
      (node (ref "C17") (pin "1") (pinfunction "1_1") (pintype "passive"))
      (node (ref "R12") (pin "2") (pinfunction "2_2") (pintype "passive"))
      (node (ref "ZQ2") (pin "2") (pinfunction "Out/In_2") (pintype "passive"))
    )
    (net (code "44") (name "VDD") (class "Default")
      (node (ref "C11") (pin "2") (pinfunction "2_2") (pintype "passive"))
      (node (ref "C12") (pin "1") (pinfunction "1_1") (pintype "passive"))
      (node (ref "C3") (pin "2") (pinfunction "2_2") (pintype "passive"))
      (node (ref "C4") (pin "2") (pinfunction "2_2") (pintype "passive"))
      (node (ref "C5") (pin "2") (pinfunction "2_2") (pintype "passive"))
      (node (ref "C6") (pin "2") (pinfunction "2_2") (pintype "passive"))
      (node (ref "C7") (pin "2") (pinfunction "2_2") (pintype "passive"))
      (node (ref "C8") (pin "1") (pinfunction "1_1") (pintype "passive"))
      (node (ref "DD1") (pin "100") (pinfunction "VDD3_100") (pintype "passive"))
      (node (ref "DD1") (pin "11") (pinfunction "VDD5_11") (pintype "passive"))
      (node (ref "DD1") (pin "19") (pinfunction "VDD12_19") (pintype "passive"))
      (node (ref "DD1") (pin "28") (pinfunction "VDD4_28") (pintype "passive"))
      (node (ref "DD1") (pin "50") (pinfunction "VDD1_50") (pintype "passive"))
      (node (ref "DD1") (pin "75") (pinfunction "VDD2_75") (pintype "passive"))
      (node (ref "L1") (pin "1") (pinfunction "1_1") (pintype "passive"))
      (node (ref "R2") (pin "2") (pinfunction "2_2") (pintype "passive"))
      (node (ref "R20") (pin "2") (pinfunction "2_2") (pintype "passive"))
      (node (ref "R25") (pin "2") (pinfunction "2_2") (pintype "passive"))
      (node (ref "R30") (pin "2") (pinfunction "2_2") (pintype "passive"))
      (node (ref "R4") (pin "2") (pinfunction "2_2") (pintype "passive"))
      (node (ref "R6") (pin "1") (pinfunction "1_1") (pintype "passive"))
      (node (ref "R8") (pin "2") (pinfunction "2_2") (pintype "passive"))
      (node (ref "R9") (pin "1") (pinfunction "1_1") (pintype "passive"))
      (node (ref "SB1") (pin "1") (pinfunction "1_1") (pintype "passive"))
    )
    (net (code "45") (name "unconnected-(DD1A-NRST-Pad14)") (class "Default")
      (node (ref "DD1") (pin "14") (pinfunction "NRST_14") (pintype "passive"))
    )
    (net (code "46") (name "unconnected-(DD1A-PA0-Pad23)") (class "Default")
      (node (ref "DD1") (pin "23") (pinfunction "PA0_23") (pintype "passive"))
    )
    (net (code "47") (name "unconnected-(DD1A-PA1-Pad24)") (class "Default")
      (node (ref "DD1") (pin "24") (pinfunction "PA1_24") (pintype "passive"))
    )
    (net (code "48") (name "unconnected-(DD1A-PA2-Pad25)") (class "Default")
      (node (ref "DD1") (pin "25") (pinfunction "PA2_25") (pintype "passive"))
    )
    (net (code "49") (name "unconnected-(DD1A-PA3-Pad26)") (class "Default")
      (node (ref "DD1") (pin "26") (pinfunction "PA3_26") (pintype "passive"))
    )
    (net (code "50") (name "unconnected-(DD1A-PA4-Pad29)") (class "Default")
      (node (ref "DD1") (pin "29") (pinfunction "PA4_29") (pintype "passive"))
    )
    (net (code "51") (name "unconnected-(DD1A-PA5-Pad30)") (class "Default")
      (node (ref "DD1") (pin "30") (pinfunction "PA5_30") (pintype "passive"))
    )
    (net (code "52") (name "unconnected-(DD1A-PA6-Pad31)") (class "Default")
      (node (ref "DD1") (pin "31") (pinfunction "PA6_31") (pintype "passive"))
    )
    (net (code "53") (name "unconnected-(DD1A-PA7-Pad32)") (class "Default")
      (node (ref "DD1") (pin "32") (pinfunction "PA7_32") (pintype "passive"))
    )
    (net (code "54") (name "unconnected-(DD1A-PA8-Pad67)") (class "Default")
      (node (ref "DD1") (pin "67") (pinfunction "PA8_67") (pintype "passive"))
    )
    (net (code "55") (name "unconnected-(DD1A-PA9-Pad68)") (class "Default")
      (node (ref "DD1") (pin "68") (pinfunction "PA9_68") (pintype "passive"))
    )
    (net (code "56") (name "unconnected-(DD1A-PA10-Pad69)") (class "Default")
      (node (ref "DD1") (pin "69") (pinfunction "PA10_69") (pintype "passive"))
    )
    (net (code "57") (name "unconnected-(DD1A-PA11-Pad70)") (class "Default")
      (node (ref "DD1") (pin "70") (pinfunction "PA11_70") (pintype "passive"))
    )
    (net (code "58") (name "unconnected-(DD1A-PA12-Pad71)") (class "Default")
      (node (ref "DD1") (pin "71") (pinfunction "PA12_71") (pintype "passive"))
    )
    (net (code "59") (name "unconnected-(DD1A-PA13-Pad72)") (class "Default")
      (node (ref "DD1") (pin "72") (pinfunction "PA13_72") (pintype "passive"))
    )
    (net (code "60") (name "unconnected-(DD1A-PA14-Pad76)") (class "Default")
      (node (ref "DD1") (pin "76") (pinfunction "PA14_76") (pintype "passive"))
    )
    (net (code "61") (name "unconnected-(DD1A-PA15-Pad77)") (class "Default")
      (node (ref "DD1") (pin "77") (pinfunction "PA15_77") (pintype "passive"))
    )
    (net (code "62") (name "unconnected-(DD1A-PB0-Pad35)") (class "Default")
      (node (ref "DD1") (pin "35") (pinfunction "PB0_35") (pintype "passive"))
    )
    (net (code "63") (name "unconnected-(DD1A-PB1-Pad36)") (class "Default")
      (node (ref "DD1") (pin "36") (pinfunction "PB1_36") (pintype "passive"))
    )
    (net (code "64") (name "unconnected-(DD1A-PB2-Pad37)") (class "Default")
      (node (ref "DD1") (pin "37") (pinfunction "PB2_37") (pintype "passive"))
    )
    (net (code "65") (name "unconnected-(DD1A-PB3-Pad89)") (class "Default")
      (node (ref "DD1") (pin "89") (pinfunction "PB3_89") (pintype "passive"))
    )
    (net (code "66") (name "unconnected-(DD1A-PB4-Pad90)") (class "Default")
      (node (ref "DD1") (pin "90") (pinfunction "PB4_90") (pintype "passive"))
    )
    (net (code "67") (name "unconnected-(DD1A-PB5-Pad91)") (class "Default")
      (node (ref "DD1") (pin "91") (pinfunction "PB5_91") (pintype "passive"))
    )
    (net (code "68") (name "unconnected-(DD1A-PB7-Pad93)") (class "Default")
      (node (ref "DD1") (pin "93") (pinfunction "PB7_93") (pintype "passive"))
    )
    (net (code "69") (name "unconnected-(DD1A-PB8-Pad95)") (class "Default")
      (node (ref "DD1") (pin "95") (pinfunction "PB8_95") (pintype "passive"))
    )
    (net (code "70") (name "unconnected-(DD1A-PB10-Pad47)") (class "Default")
      (node (ref "DD1") (pin "47") (pinfunction "PB10_47") (pintype "passive"))
    )
    (net (code "71") (name "unconnected-(DD1A-PB11-Pad48)") (class "Default")
      (node (ref "DD1") (pin "48") (pinfunction "PB11_48") (pintype "passive"))
    )
    (net (code "72") (name "unconnected-(DD1A-PB12-Pad51)") (class "Default")
      (node (ref "DD1") (pin "51") (pinfunction "PB12_51") (pintype "passive"))
    )
    (net (code "73") (name "unconnected-(DD1A-PB13-Pad52)") (class "Default")
      (node (ref "DD1") (pin "52") (pinfunction "PB13_52") (pintype "passive"))
    )
    (net (code "74") (name "unconnected-(DD1A-PB14-Pad53)") (class "Default")
      (node (ref "DD1") (pin "53") (pinfunction "PB14_53") (pintype "passive"))
    )
    (net (code "75") (name "unconnected-(DD1A-PB15-Pad54)") (class "Default")
      (node (ref "DD1") (pin "54") (pinfunction "PB15_54") (pintype "passive"))
    )
    (net (code "76") (name "unconnected-(DD1A-PC0-Pad15)") (class "Default")
      (node (ref "DD1") (pin "15") (pinfunction "PC0_15") (pintype "passive"))
    )
    (net (code "77") (name "unconnected-(DD1A-PC1-Pad16)") (class "Default")
      (node (ref "DD1") (pin "16") (pinfunction "PC1_16") (pintype "passive"))
    )
    (net (code "78") (name "unconnected-(DD1A-PC2-Pad17)") (class "Default")
      (node (ref "DD1") (pin "17") (pinfunction "PC2_17") (pintype "passive"))
    )
    (net (code "79") (name "unconnected-(DD1A-PC3-Pad18)") (class "Default")
      (node (ref "DD1") (pin "18") (pinfunction "PC3_18") (pintype "passive"))
    )
    (net (code "80") (name "unconnected-(DD1A-PC4-Pad33)") (class "Default")
      (node (ref "DD1") (pin "33") (pinfunction "PC4_33") (pintype "passive"))
    )
    (net (code "81") (name "unconnected-(DD1A-PC5-Pad34)") (class "Default")
      (node (ref "DD1") (pin "34") (pinfunction "PC5_34") (pintype "passive"))
    )
    (net (code "82") (name "unconnected-(DD1A-PC6-Pad63)") (class "Default")
      (node (ref "DD1") (pin "63") (pinfunction "PC6_63") (pintype "passive"))
    )
    (net (code "83") (name "unconnected-(DD1A-PC7-Pad64)") (class "Default")
      (node (ref "DD1") (pin "64") (pinfunction "PC7_64") (pintype "passive"))
    )
    (net (code "84") (name "unconnected-(DD1A-PC8-Pad65)") (class "Default")
      (node (ref "DD1") (pin "65") (pinfunction "PC8_65") (pintype "passive"))
    )
    (net (code "85") (name "unconnected-(DD1A-PC9-Pad66)") (class "Default")
      (node (ref "DD1") (pin "66") (pinfunction "PC9_66") (pintype "passive"))
    )
    (net (code "86") (name "unconnected-(DD1A-PC10-Pad78)") (class "Default")
      (node (ref "DD1") (pin "78") (pinfunction "PC10_78") (pintype "passive"))
    )
    (net (code "87") (name "unconnected-(DD1A-PC11-Pad79)") (class "Default")
      (node (ref "DD1") (pin "79") (pinfunction "PC11_79") (pintype "passive"))
    )
    (net (code "88") (name "unconnected-(DD1A-PC12-Pad80)") (class "Default")
      (node (ref "DD1") (pin "80") (pinfunction "PC12_80") (pintype "passive"))
    )
    (net (code "89") (name "unconnected-(DD1A-PC13-Pad7)") (class "Default")
      (node (ref "DD1") (pin "7") (pinfunction "PC13_7") (pintype "passive"))
    )
    (net (code "90") (name "unconnected-(DD1A-PD0-Pad81)") (class "Default")
      (node (ref "DD1") (pin "81") (pinfunction "PD0_81") (pintype "passive"))
    )
    (net (code "91") (name "unconnected-(DD1A-PD1-Pad82)") (class "Default")
      (node (ref "DD1") (pin "82") (pinfunction "PD1_82") (pintype "passive"))
    )
    (net (code "92") (name "unconnected-(DD1A-PD2-Pad83)") (class "Default")
      (node (ref "DD1") (pin "83") (pinfunction "PD2_83") (pintype "passive"))
    )
    (net (code "93") (name "unconnected-(DD1A-PD3-Pad84)") (class "Default")
      (node (ref "DD1") (pin "84") (pinfunction "PD3_84") (pintype "passive"))
    )
    (net (code "94") (name "unconnected-(DD1A-PD4-Pad85)") (class "Default")
      (node (ref "DD1") (pin "85") (pinfunction "PD4_85") (pintype "passive"))
    )
    (net (code "95") (name "unconnected-(DD1A-PD5-Pad86)") (class "Default")
      (node (ref "DD1") (pin "86") (pinfunction "PD5_86") (pintype "passive"))
    )
    (net (code "96") (name "unconnected-(DD1A-PD6-Pad87)") (class "Default")
      (node (ref "DD1") (pin "87") (pinfunction "PD6_87") (pintype "passive"))
    )
    (net (code "97") (name "unconnected-(DD1A-PD7-Pad88)") (class "Default")
      (node (ref "DD1") (pin "88") (pinfunction "PD7_88") (pintype "passive"))
    )
    (net (code "98") (name "unconnected-(DD1A-PD8-Pad55)") (class "Default")
      (node (ref "DD1") (pin "55") (pinfunction "PD8_55") (pintype "passive"))
    )
    (net (code "99") (name "unconnected-(DD1A-PD9-Pad56)") (class "Default")
      (node (ref "DD1") (pin "56") (pinfunction "PD9_56") (pintype "passive"))
    )
    (net (code "100") (name "unconnected-(DD1A-PD10-Pad57)") (class "Default")
      (node (ref "DD1") (pin "57") (pinfunction "PD10_57") (pintype "passive"))
    )
    (net (code "101") (name "unconnected-(DD1A-PD11-Pad58)") (class "Default")
      (node (ref "DD1") (pin "58") (pinfunction "PD11_58") (pintype "passive"))
    )
    (net (code "102") (name "unconnected-(DD1A-PD12-Pad59)") (class "Default")
      (node (ref "DD1") (pin "59") (pinfunction "PD12_59") (pintype "passive"))
    )
    (net (code "103") (name "unconnected-(DD1A-PD13-Pad60)") (class "Default")
      (node (ref "DD1") (pin "60") (pinfunction "PD13_60") (pintype "passive"))
    )
    (net (code "104") (name "unconnected-(DD1A-PD14-Pad61)") (class "Default")
      (node (ref "DD1") (pin "61") (pinfunction "PD14_61") (pintype "passive"))
    )
    (net (code "105") (name "unconnected-(DD1A-PD15-Pad62)") (class "Default")
      (node (ref "DD1") (pin "62") (pinfunction "PD15_62") (pintype "passive"))
    )
    (net (code "106") (name "unconnected-(DD1A-PE0-Pad97)") (class "Default")
      (node (ref "DD1") (pin "97") (pinfunction "PE0_97") (pintype "passive"))
    )
    (net (code "107") (name "unconnected-(DD1A-PE1-Pad98)") (class "Default")
      (node (ref "DD1") (pin "98") (pinfunction "PE1_98") (pintype "passive"))
    )
    (net (code "108") (name "unconnected-(DD1A-PE2-Pad1)") (class "Default")
      (node (ref "DD1") (pin "1") (pinfunction "PE2_1") (pintype "passive"))
    )
    (net (code "109") (name "unconnected-(DD1A-PE3-Pad2)") (class "Default")
      (node (ref "DD1") (pin "2") (pinfunction "PE3_2") (pintype "passive"))
    )
    (net (code "110") (name "unconnected-(DD1A-PE4-Pad3)") (class "Default")
      (node (ref "DD1") (pin "3") (pinfunction "PE4_3") (pintype "passive"))
    )
    (net (code "111") (name "unconnected-(DD1A-PE5-Pad4)") (class "Default")
      (node (ref "DD1") (pin "4") (pinfunction "PE5_4") (pintype "passive"))
    )
    (net (code "112") (name "unconnected-(DD1A-PE6-Pad5)") (class "Default")
      (node (ref "DD1") (pin "5") (pinfunction "PE6_5") (pintype "passive"))
    )
    (net (code "113") (name "unconnected-(DD1A-PE7-Pad38)") (class "Default")
      (node (ref "DD1") (pin "38") (pinfunction "PE7_38") (pintype "passive"))
    )
    (net (code "114") (name "unconnected-(DD1A-PE8-Pad39)") (class "Default")
      (node (ref "DD1") (pin "39") (pinfunction "PE8_39") (pintype "passive"))
    )
    (net (code "115") (name "unconnected-(DD1A-PE9-Pad40)") (class "Default")
      (node (ref "DD1") (pin "40") (pinfunction "PE9_40") (pintype "passive"))
    )
    (net (code "116") (name "unconnected-(DD1A-PE10-Pad41)") (class "Default")
      (node (ref "DD1") (pin "41") (pinfunction "PE10_41") (pintype "passive"))
    )
    (net (code "117") (name "unconnected-(DD1A-PE11-Pad42)") (class "Default")
      (node (ref "DD1") (pin "42") (pinfunction "PE11_42") (pintype "passive"))
    )
    (net (code "118") (name "unconnected-(DD1A-PE12-Pad43)") (class "Default")
      (node (ref "DD1") (pin "43") (pinfunction "PE12_43") (pintype "passive"))
    )
    (net (code "119") (name "unconnected-(DD1A-PE13-Pad44)") (class "Default")
      (node (ref "DD1") (pin "44") (pinfunction "PE13_44") (pintype "passive"))
    )
    (net (code "120") (name "unconnected-(DD1A-PE14-Pad45)") (class "Default")
      (node (ref "DD1") (pin "45") (pinfunction "PE14_45") (pintype "passive"))
    )
    (net (code "121") (name "unconnected-(DD1A-PE15-Pad46)") (class "Default")
      (node (ref "DD1") (pin "46") (pinfunction "PE15_46") (pintype "passive"))
    )
    (net (code "122") (name "unconnected-(HL1-DB0-Pad7)") (class "Default")
      (node (ref "HL1") (pin "7") (pinfunction "DB0_7") (pintype "passive"))
    )
    (net (code "123") (name "unconnected-(HL1-DB1-Pad8)") (class "Default")
      (node (ref "HL1") (pin "8") (pinfunction "DB1_8") (pintype "passive"))
    )
    (net (code "124") (name "unconnected-(HL1-DB2-Pad9)") (class "Default")
      (node (ref "HL1") (pin "9") (pinfunction "DB2_9") (pintype "passive"))
    )
    (net (code "125") (name "unconnected-(HL1-DB3-Pad10)") (class "Default")
      (node (ref "HL1") (pin "10") (pinfunction "DB3_10") (pintype "passive"))
    )
  )
)
